# Sheet2.net
KiCad netlist of a schematic drawn in Altium Designer
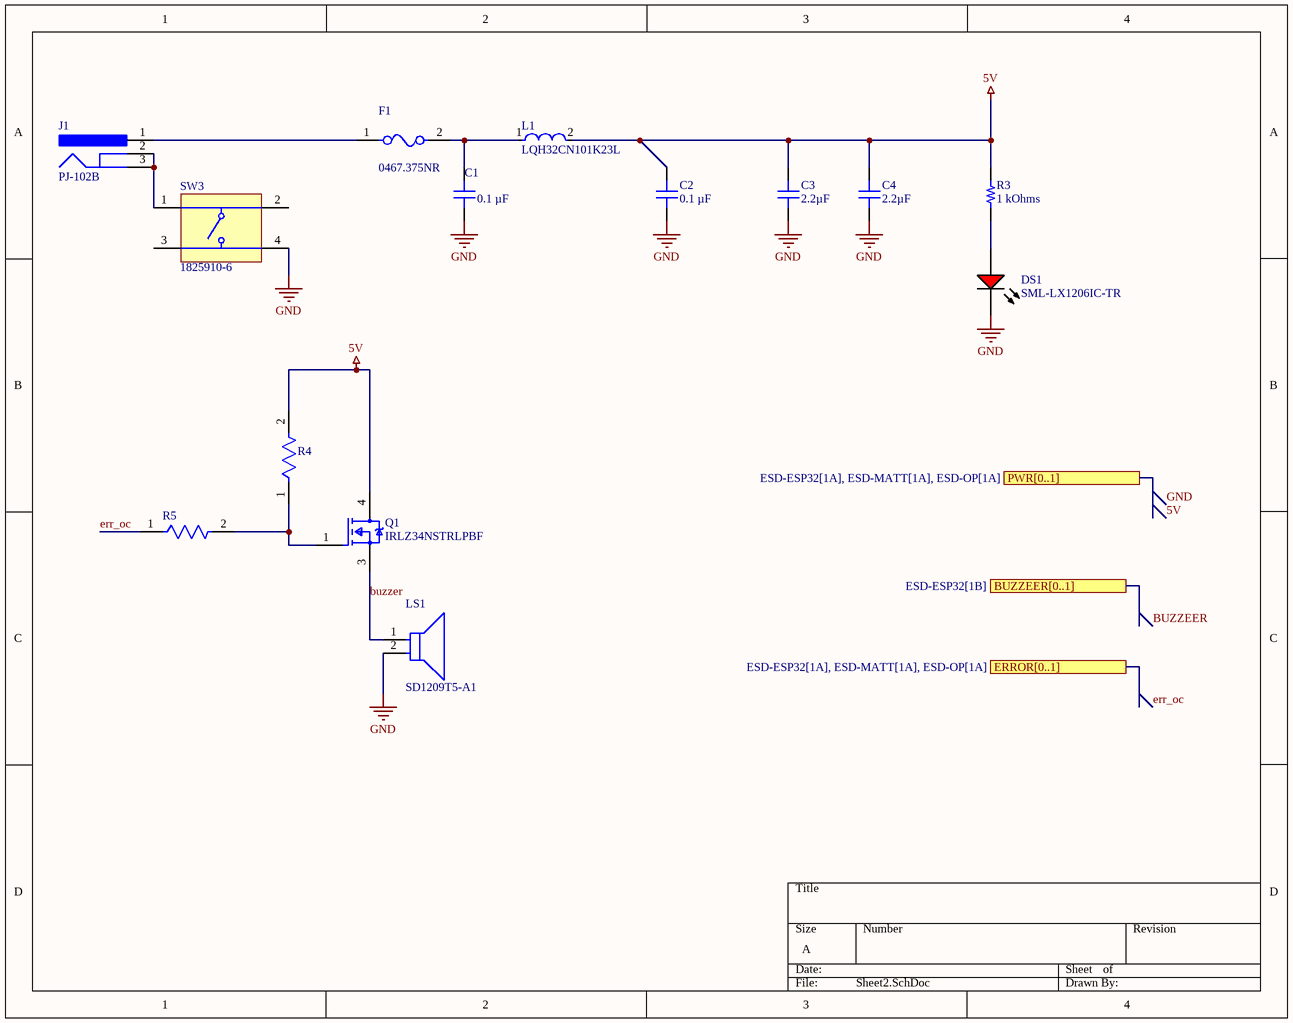
[diagram p0: Sheet2.SchDoc]

(export (version "E")
  (design (tool "Eeschema 10.0.6"))
  (components
    (comp (ref "C1")
      (value "0.1 µF")
      (footprint "CAP 0603_1608")
      (description "CAP CER 0.1UF 50V X7R 0603")
      (fields (field (name "PART NUMBER") "C0603X104J5RACAUTO") (field (name "MANUFACTURER") "KEMET"))
      (libsource (lib "Celestial Altium Library - altium_library") (part "Capacitor"))
    )
    (comp (ref "C2")
      (value "0.1 µF")
      (footprint "CAP 0603_1608")
      (description "CAP CER 0.1UF 50V X7R 0603")
      (fields (field (name "PART NUMBER") "C0603X104J5RACAUTO") (field (name "MANUFACTURER") "KEMET"))
      (libsource (lib "Celestial Altium Library - altium_library") (part "Capacitor"))
    )
    (comp (ref "C3")
      (value "2.2µF")
      (footprint "CAP 0603_1608")
      (description "CAP CER 2.2UF 10V X7R 0603")
      (fields (field (name "PART NUMBER") "0603ZC225KAT2A") (field (name "MANUFACTURER") "AVX Corporation"))
      (libsource (lib "Celestial Altium Library - altium_library") (part "Capacitor"))
    )
    (comp (ref "C4")
      (value "2.2µF")
      (footprint "CAP 0603_1608")
      (description "CAP CER 2.2UF 10V X7R 0603")
      (fields (field (name "PART NUMBER") "0603ZC225KAT2A") (field (name "MANUFACTURER") "AVX Corporation"))
      (libsource (lib "Celestial Altium Library - altium_library") (part "Capacitor"))
    )
    (comp (ref "DS1")
      (value "SML-LX1206IC-TR")
      (footprint "LUMX-SML-LX1206IC_V")
      (description "LED Red, 65 mW, -40 to 85 degC, 2-Pin SMD, RoHS, Tape and Reel")
      (fields (field (name "MANUFACTURER") "Lumex"))
      (libsource (lib "Altium Content Vault") (part "LED-RED-AK-2"))
    )
    (comp (ref "F1")
      (value "0467.375NR")
      (footprint "FP-467-MFG")
      (description "FUSE BOARD MOUNT 375MA 32VAC/VDC")
      (fields
        (field (name "OCTOPART") "https://octopart.com/0467.375nr-littelfuse-565971")
        (field (name "MANUFACTURER") "Littelfuse")
      )
      (libsource (lib "Altium Content Vault") (part "5bcf9b9f640e542cf0359d10258e979"))
    )
    (comp (ref "J1")
      (value "PJ-102B")
      (footprint "CUI-PJ-102B_V")
      (fields (field (name "MANUFACTURER") "CUIInc."))
      (libsource (lib "Altium Content Vault") (part "JACK-2CD3-RN"))
    )
    (comp (ref "L1")
      (value "LQH32CN101K23L")
      (footprint "FP-LQH32CH_23-MFG")
      (description "Wire Wound Ferrite Inductor for Power Lines 100μH ±10% 4.55Ω 100mA 1210")
      (fields (field (name "TOLERANCE") "10%"))
      (libsource (lib "Altium Content Vault") (part "725321dda6339637d4d059423bc1c3c"))
    )
    (comp (ref "LS1")
      (value "SD1209T5-A1")
      (footprint "FP-SD1209-MFG")
      (description "AUDIO MAGNETIC XDCR 3-6V TH")
      (libsource (lib "Altium Content Vault") (part "1973c4b650225fd2ddacaff6b763965"))
    )
    (comp (ref "Q1")
      (value "IRLZ34NSTRLPBF")
      (footprint "FP-PG-TO263-3-MFG")
      (description "MOSFET N-CH 55V 30A D2PAK")
      (libsource (lib "Altium Content Vault") (part "d7870aa5ef5e57eb3883acff98ff17f"))
    )
    (comp (ref "R3")
      (value "1 kOhms")
      (footprint "KOA RES RK73 RN73 0402_1005")
      (description "RES 1K OHM 1% 1/10W 0402")
      (fields
        (field (name "PART NUMBER") "RK73H1ETTPB1001F")
        (field (name "MANUFACTURER") "KOA Speer Electronics, Inc.")
      )
      (libsource (lib "Celestial Altium Library - altium_library") (part "Resistor"))
    )
    (comp (ref "R4")
      (value "AC0603FR-072KL")
      (footprint "FP-AC0603-IPC_B")
      (description "RES 2kΩ 1.00% 0.1W 0603")
      (fields (field (name "TOLERANCE") "1%"))
      (libsource (lib "Altium Content Vault") (part "1029c3af85768c4190bb7ad29bc67b5"))
    )
    (comp (ref "R5")
      (value "AC0603FR-072KL")
      (footprint "FP-AC0603-IPC_B")
      (description "RES 2kΩ 1.00% 0.1W 0603")
      (fields (field (name "TOLERANCE") "1%"))
      (libsource (lib "Altium Content Vault") (part "1029c3af85768c4190bb7ad29bc67b5"))
    )
    (comp (ref "SW3")
      (value "1825910-6")
      (footprint "TECO-1825910-6_V")
      (description "Tact Switch, SPST-NO, 0.05 A, -35 to 85 degC, 4-Pin THD, RoHS, Bulk")
      (fields (field (name "MANUFACTURER") "TE Connectivity"))
      (libsource (lib "Altium Content Vault") (part "SW-SPST-4_A"))
    )
  )
  (nets
    (net (code "11") (name "/buzzer") (class "Default")
      (node (ref "LS1") (pin "1") (pinfunction "C_1") (pintype "passive"))
      (node (ref "Q1") (pin "3") (pinfunction "S_3") (pintype "passive"))
    )
    (net (code "12") (name "/err_oc") (class "Default")
      (node (ref "R5") (pin "1") (pinfunction "1_1") (pintype "passive"))
    )
    (net (code "13") (name "5V") (class "Default")
      (node (ref "C2") (pin "2") (pinfunction "2_2") (pintype "passive"))
      (node (ref "C3") (pin "2") (pinfunction "2_2") (pintype "passive"))
      (node (ref "C4") (pin "2") (pinfunction "2_2") (pintype "passive"))
      (node (ref "L1") (pin "2") (pinfunction "2_2") (pintype "passive"))
      (node (ref "Q1") (pin "4") (pinfunction "D_4") (pintype "passive"))
      (node (ref "R3") (pin "2") (pinfunction "2_2") (pintype "passive"))
      (node (ref "R4") (pin "2") (pinfunction "2_2") (pintype "passive"))
    )
    (net (code "14") (name "GND") (class "Default")
      (node (ref "C1") (pin "1") (pinfunction "1_1") (pintype "passive"))
      (node (ref "C2") (pin "1") (pinfunction "1_1") (pintype "passive"))
      (node (ref "C3") (pin "1") (pinfunction "1_1") (pintype "passive"))
      (node (ref "C4") (pin "1") (pinfunction "1_1") (pintype "passive"))
      (node (ref "DS1") (pin "2") (pinfunction "K_2") (pintype "passive"))
      (node (ref "LS1") (pin "2") (pinfunction "A_2") (pintype "passive"))
      (node (ref "SW3") (pin "4") (pinfunction "4_4") (pintype "passive"))
    )
    (net (code "15") (name "Net-(C1-Pad2)") (class "Default")
      (node (ref "C1") (pin "2") (pinfunction "2_2") (pintype "passive"))
      (node (ref "F1") (pin "2") (pinfunction "2_2") (pintype "passive"))
      (node (ref "L1") (pin "1") (pinfunction "1_1") (pintype "passive"))
    )
    (net (code "16") (name "Net-(DS1-A)") (class "Default")
      (node (ref "DS1") (pin "1") (pinfunction "A_1") (pintype "passive"))
      (node (ref "R3") (pin "1") (pinfunction "1_1") (pintype "passive"))
    )
    (net (code "17") (name "Net-(F1-Pad1)") (class "Default")
      (node (ref "F1") (pin "1") (pinfunction "1_1") (pintype "passive"))
      (node (ref "J1") (pin "1") (pinfunction "1_1") (pintype "passive"))
    )
    (net (code "18") (name "Net-(J1-Pad2)") (class "Default")
      (node (ref "J1") (pin "2") (pinfunction "2_2") (pintype "passive"))
      (node (ref "J1") (pin "3") (pinfunction "3_3") (pintype "passive"))
      (node (ref "SW3") (pin "1") (pinfunction "1_1") (pintype "passive"))
    )
    (net (code "19") (name "Net-(Q1-G)") (class "Default")
      (node (ref "Q1") (pin "1") (pinfunction "G_1") (pintype "passive"))
      (node (ref "R4") (pin "1") (pinfunction "1_1") (pintype "passive"))
      (node (ref "R5") (pin "2") (pinfunction "2_2") (pintype "passive"))
    )
    (net (code "20") (name "unconnected-(SW3-Pad2)") (class "Default")
      (node (ref "SW3") (pin "2") (pinfunction "2_2") (pintype "passive"))
    )
    (net (code "21") (name "unconnected-(SW3-Pad3)") (class "Default")
      (node (ref "SW3") (pin "3") (pinfunction "3_3") (pintype "passive"))
    )
  )
)
